# PowerCOnverter_v1_0.net
KiCad netlist of a schematic drawn in EAGLE
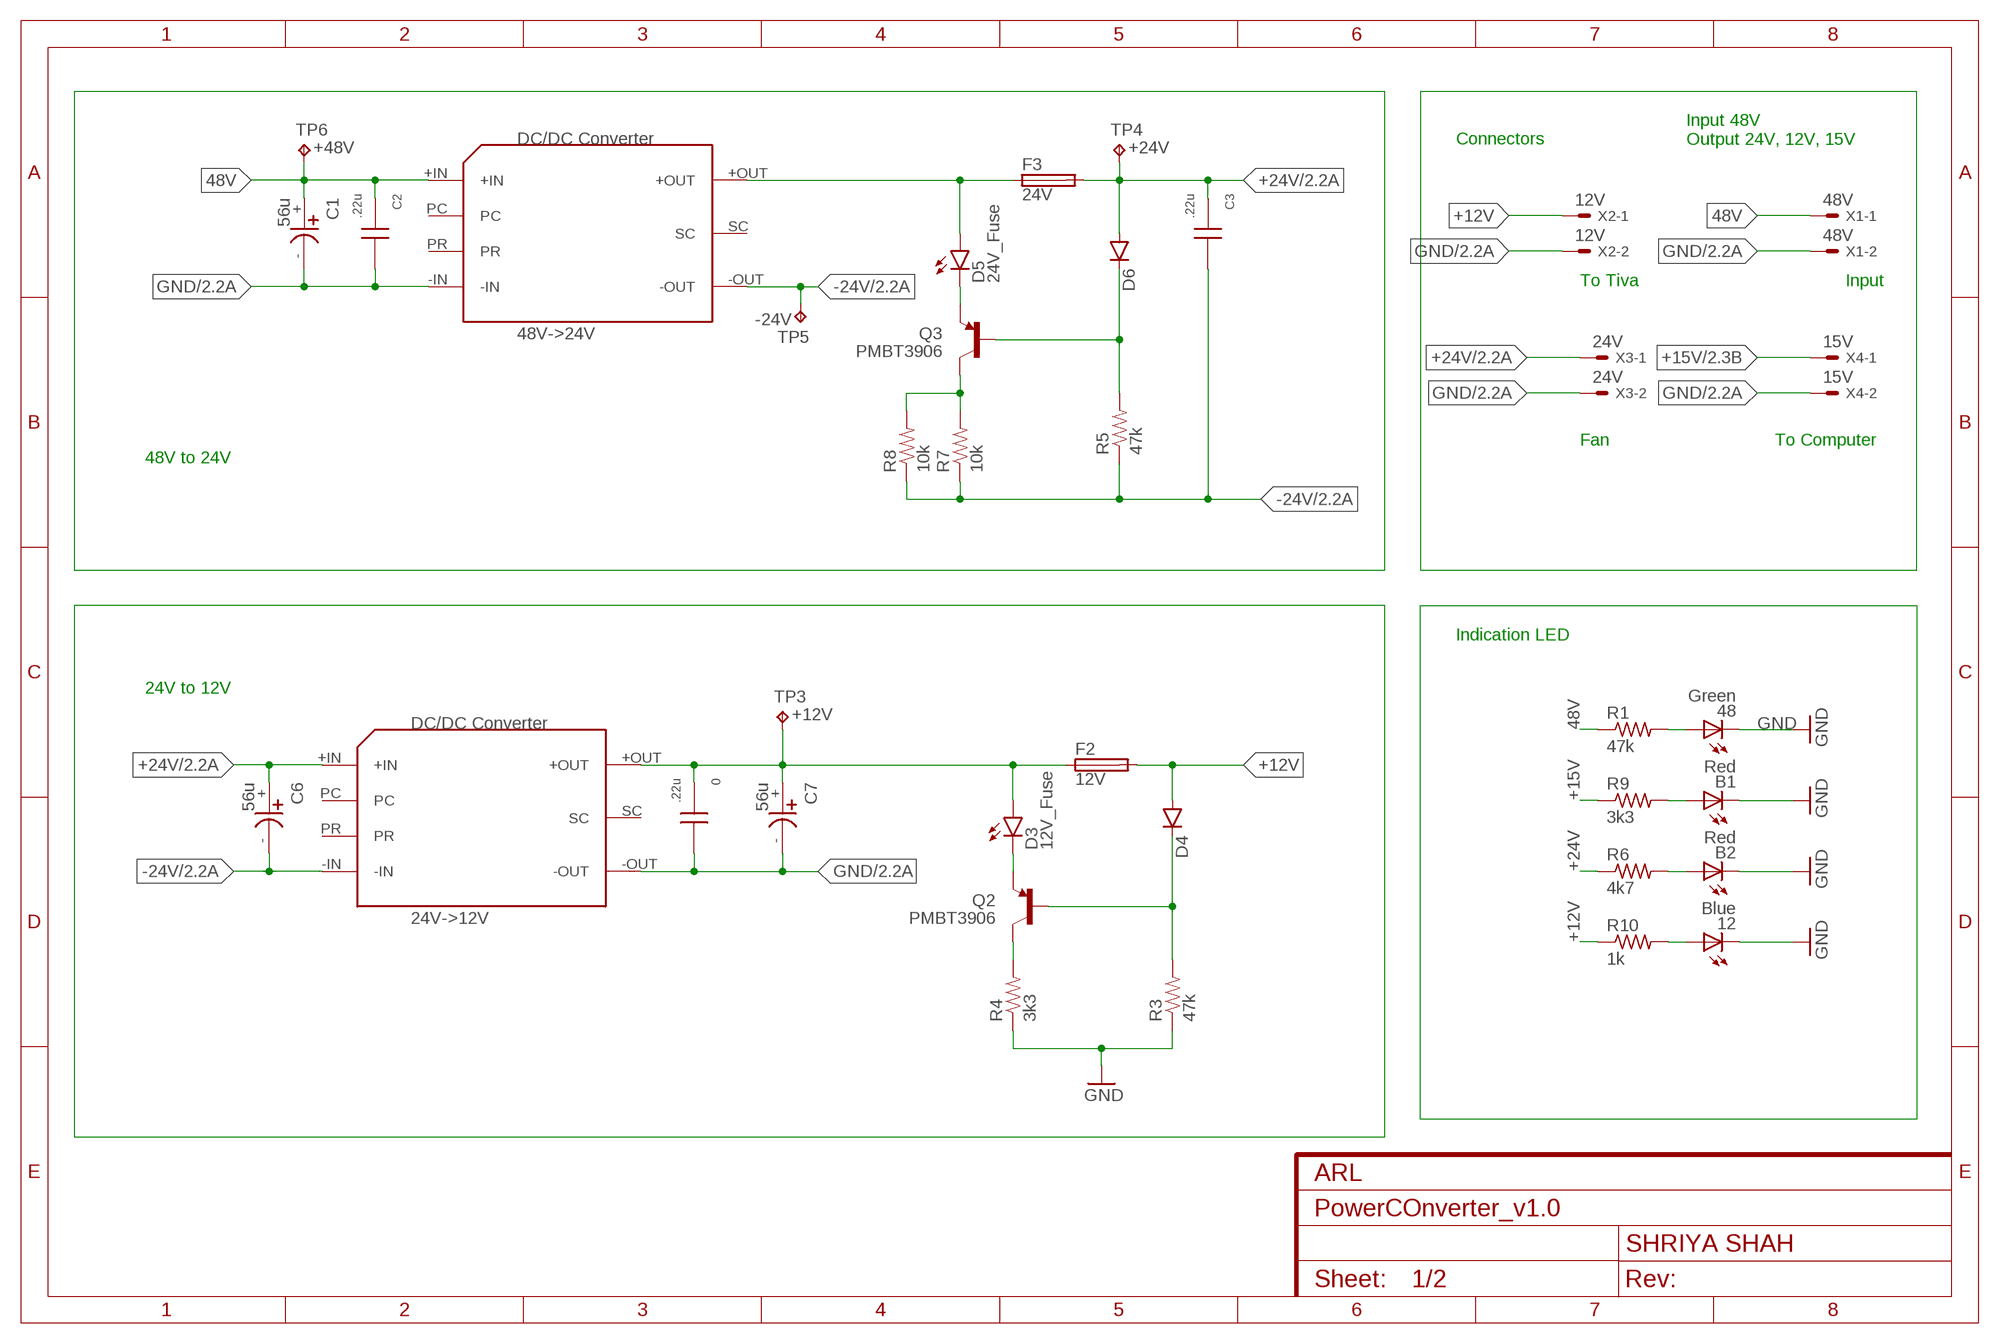
[diagram p0: schematic, sheet 1]
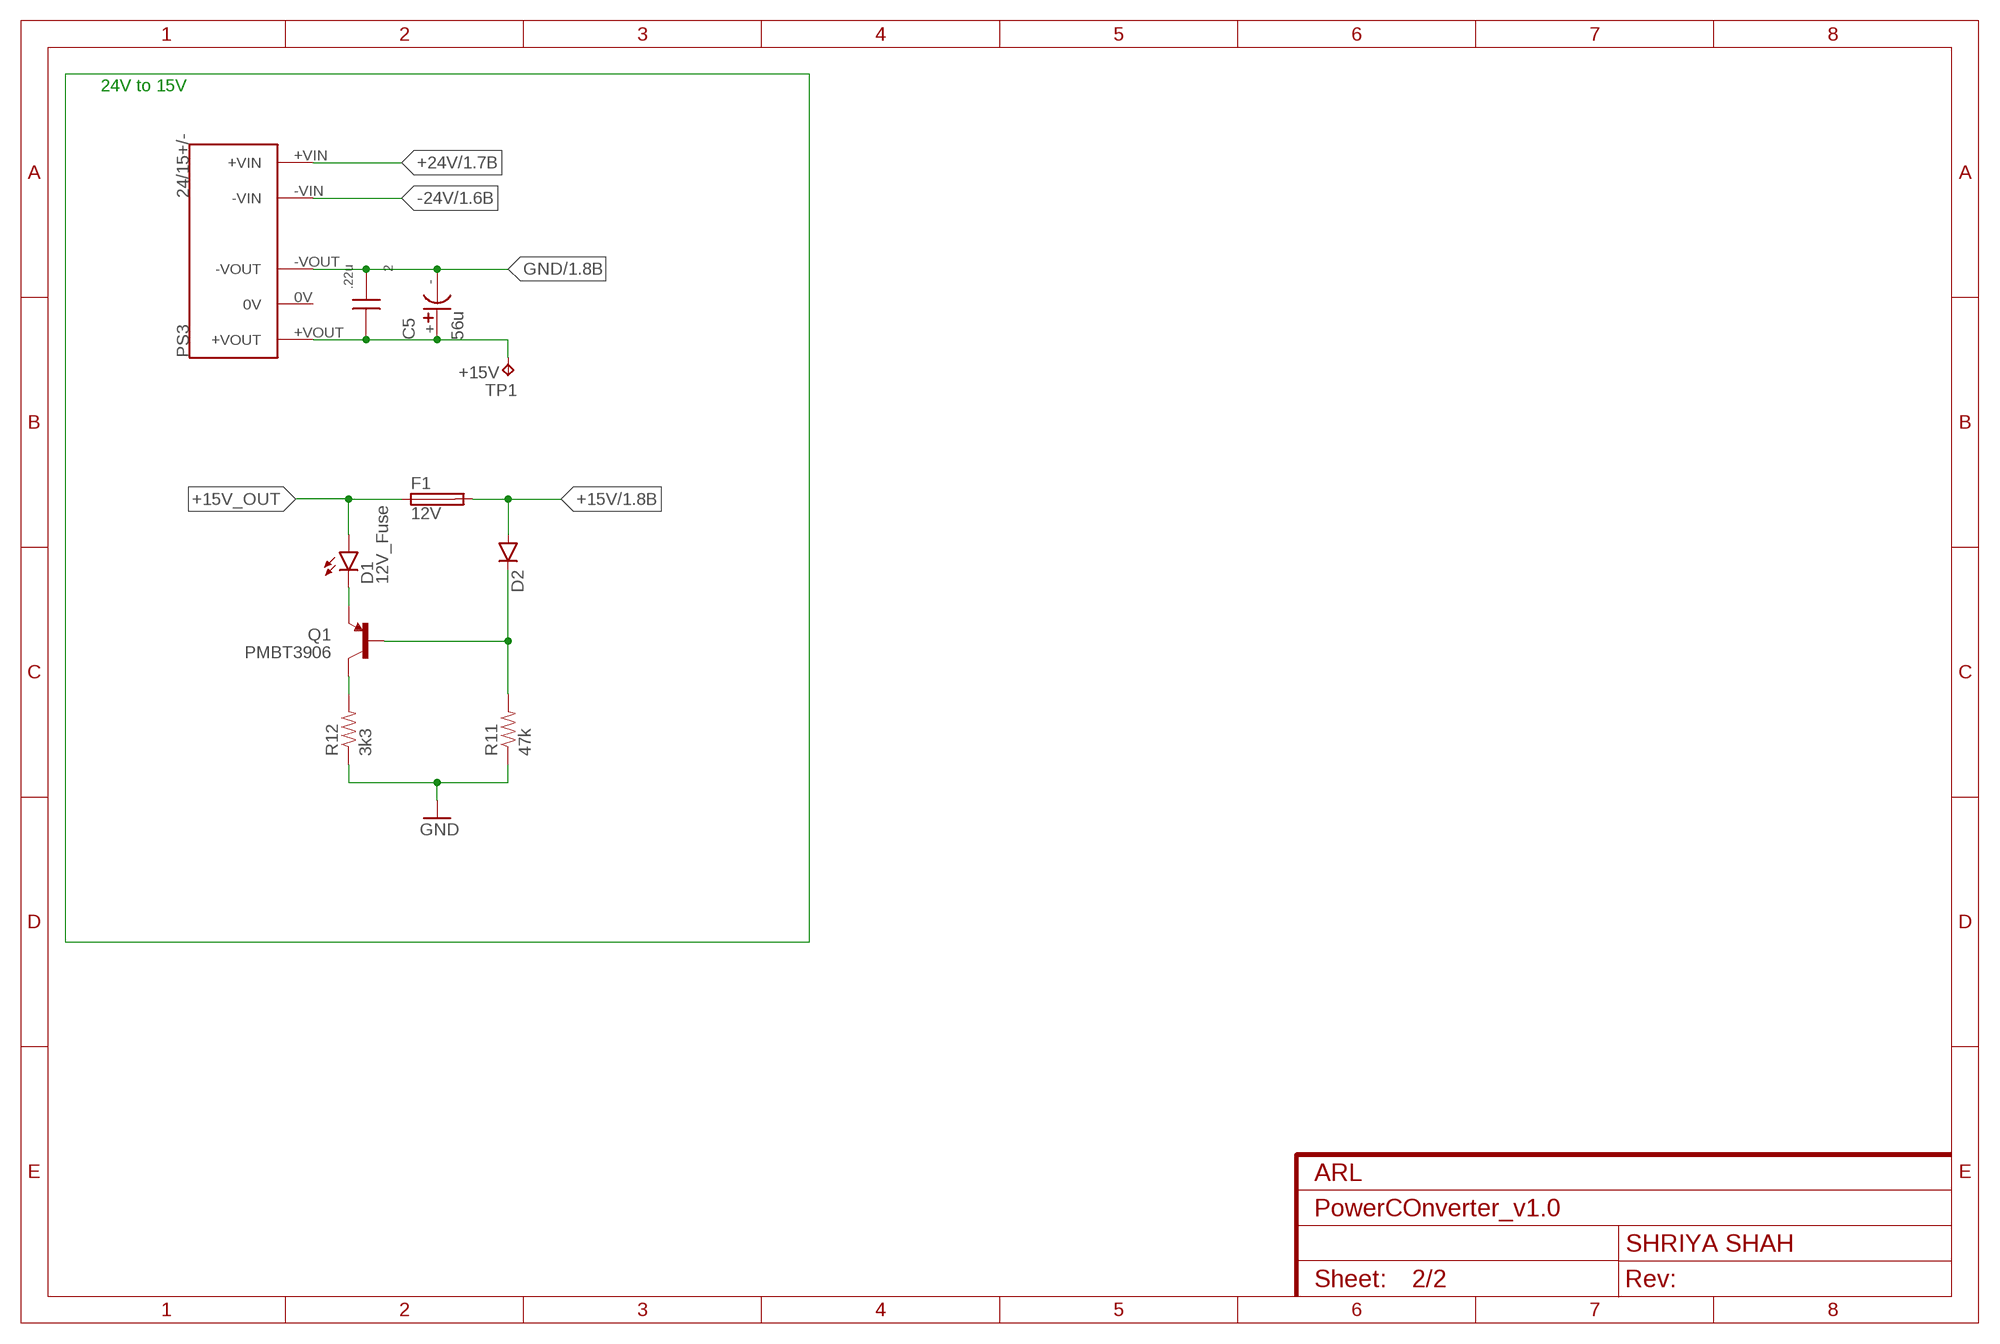
[diagram p1: schematic, sheet 2]

(export (version "E")
  (design (tool "Eeschema 10.0.6"))
  (components
    (comp (ref "2")
      (value ".22u")
      (footprint "eagle-import:CERAMIC_CAP_5MM-LEAD")
      (fields (field (name "MPN") "FK26X7R2A224K "))
      (libsource (lib "eagle-import") (part ".22U_100VDC_CERAMIC_CAP"))
    )
    (comp (ref "C5")
      (value "56u")
      (footprint "eagle-import:CAP_5MM-LEAD-10MM-D")
      (fields (field (name "MPN") "UPJ2A560MPD1TD"))
      (libsource (lib "eagle-import") (part "56U_100VDC_NICHICON"))
    )
    (comp (ref "D1")
      (value "12V_Fuse")
      (footprint "eagle-import:LED-0603")
      (fields (field (name "MPN") "LS L296-P2Q2-1-Z"))
      (libsource (lib "eagle-import") (part "RED_LED_0603"))
    )
    (comp (ref "D2")
      (value "DIODESOD")
      (footprint "eagle-import:SOD-323")
      (fields (field (name "MPN") "BAS16HT1G"))
      (libsource (lib "eagle-import") (part "DIODESOD"))
    )
    (comp (ref "F1")
      (value "12V")
      (footprint "eagle-import:LITTELFUSE_NANO")
      (fields (field (name "MPN") "01550900M"))
      (libsource (lib "eagle-import") (part "FUSELITTLEFUSE_NANO"))
    )
    (comp (ref "PS3")
      (value "24/15+/-")
      (footprint "eagle-import:MURATA_NMH")
      (fields (field (name "MPN") "NMH2415SC"))
      (libsource (lib "eagle-import") (part "MURATA_NMH2415SC"))
    )
    (comp (ref "Q1")
      (value "PMBT3906")
      (footprint "eagle-import:SOT23-3")
      (fields (field (name "MPN") " PMBT3906,215 "))
      (libsource (lib "eagle-import") (part "TRANSISTOR_PNPPMBT3906"))
    )
    (comp (ref "R11")
      (value "47k")
      (footprint "eagle-import:0603-RES")
      (fields (field (name "MPN") "CRCW060347K0JNEA"))
      (libsource (lib "eagle-import") (part "47K_RESISTOR_0603"))
    )
    (comp (ref "R12")
      (value "3k3")
      (footprint "eagle-import:0603-RES")
      (fields (field (name "MPN") "CRCW06033K30FKEA"))
      (libsource (lib "eagle-import") (part "3K3_RESISTOR_0603"))
    )
    (comp (ref "TP1")
      (value "+15V")
      (footprint "eagle-import:5000_SERIES_TESTPOINT")
      (fields (field (name "MPN") "5002"))
      (libsource (lib "eagle-import") (part "TP5000"))
    )
    (comp (ref "0")
      (value ".22u")
      (footprint "eagle-import:CERAMIC_CAP_5MM-LEAD")
      (fields (field (name "MPN") "FK26X7R2A224K "))
      (libsource (lib "eagle-import") (part ".22U_100VDC_CERAMIC_CAP"))
    )
    (comp (ref "12")
      (value "Blue")
      (footprint "eagle-import:CHIPLED_1206")
      (libsource (lib "eagle-import") (part "LEDCHIPLED_1206"))
    )
    (comp (ref "48")
      (value "Green")
      (footprint "eagle-import:CHIPLED_1206")
      (libsource (lib "eagle-import") (part "LEDCHIPLED_1206"))
    )
    (comp (ref "B1")
      (value "Red")
      (footprint "eagle-import:CHIPLED_1206")
      (libsource (lib "eagle-import") (part "LEDCHIPLED_1206"))
    )
    (comp (ref "B2")
      (value "Red")
      (footprint "eagle-import:CHIPLED_1206")
      (libsource (lib "eagle-import") (part "LEDCHIPLED_1206"))
    )
    (comp (ref "C1")
      (value "56u")
      (footprint "eagle-import:CAP_5MM-LEAD-10MM-D")
      (fields (field (name "MPN") "UPJ2A560MPD1TD"))
      (libsource (lib "eagle-import") (part "56U_100VDC_NICHICON"))
    )
    (comp (ref "C2")
      (value ".22u")
      (footprint "eagle-import:CERAMIC_CAP_5MM-LEAD")
      (fields (field (name "MPN") "FK26X7R2A224K "))
      (libsource (lib "eagle-import") (part ".22U_100VDC_CERAMIC_CAP"))
    )
    (comp (ref "C3")
      (value ".22u")
      (footprint "eagle-import:CERAMIC_CAP_5MM-LEAD")
      (fields (field (name "MPN") "FK26X7R2A224K "))
      (libsource (lib "eagle-import") (part ".22U_100VDC_CERAMIC_CAP"))
    )
    (comp (ref "C6")
      (value "56u")
      (footprint "eagle-import:CAP_5MM-LEAD-10MM-D")
      (fields (field (name "MPN") "UPJ2A560MPD1TD"))
      (libsource (lib "eagle-import") (part "56U_100VDC_NICHICON"))
    )
    (comp (ref "C7")
      (value "56u")
      (footprint "eagle-import:CAP_5MM-LEAD-10MM-D")
      (fields (field (name "MPN") "UPJ2A560MPD1TD"))
      (libsource (lib "eagle-import") (part "56U_100VDC_NICHICON"))
    )
    (comp (ref "D3")
      (value "12V_Fuse")
      (footprint "eagle-import:LED-0603")
      (fields (field (name "MPN") "LS L296-P2Q2-1-Z"))
      (libsource (lib "eagle-import") (part "RED_LED_0603"))
    )
    (comp (ref "D4")
      (value "DIODESOD")
      (footprint "eagle-import:SOD-323")
      (fields (field (name "MPN") "BAS16HT1G"))
      (libsource (lib "eagle-import") (part "DIODESOD"))
    )
    (comp (ref "D5")
      (value "24V_Fuse")
      (footprint "eagle-import:LED-0603")
      (fields (field (name "MPN") "LS L296-P2Q2-1-Z"))
      (libsource (lib "eagle-import") (part "RED_LED_0603"))
    )
    (comp (ref "D6")
      (value "DIODESOD")
      (footprint "eagle-import:SOD-323")
      (fields (field (name "MPN") "BAS16HT1G"))
      (libsource (lib "eagle-import") (part "DIODESOD"))
    )
    (comp (ref "F2")
      (value "12V")
      (footprint "eagle-import:LITTELFUSE_NANO")
      (fields (field (name "MPN") "01550900M"))
      (libsource (lib "eagle-import") (part "FUSELITTLEFUSE_NANO"))
    )
    (comp (ref "F3")
      (value "24V")
      (footprint "eagle-import:LITTELFUSE_NANO")
      (fields (field (name "MPN") "01550900M"))
      (libsource (lib "eagle-import") (part "FUSELITTLEFUSE_NANO"))
    )
    (comp (ref "PS1")
      (value "48V->24V")
      (footprint "eagle-import:VICOR_MICRO_DC_DC_CONVERTER")
      (fields (field (name "MPN") "V48C24C150BL"))
      (libsource (lib "eagle-import") (part "VICOR_MICRO_DC/DC_24V"))
    )
    (comp (ref "PS2")
      (value "24V->12V")
      (footprint "eagle-import:VICOR_MICRO_DC_DC_CONVERTER")
      (fields (field (name "MPN") "V24C12T100BL"))
      (libsource (lib "eagle-import") (part "VICOR_MICRO_DC/DC_12V"))
    )
    (comp (ref "Q2")
      (value "PMBT3906")
      (footprint "eagle-import:SOT23-3")
      (fields (field (name "MPN") " PMBT3906,215 "))
      (libsource (lib "eagle-import") (part "TRANSISTOR_PNPPMBT3906"))
    )
    (comp (ref "Q3")
      (value "PMBT3906")
      (footprint "eagle-import:SOT23-3")
      (fields (field (name "MPN") " PMBT3906,215 "))
      (libsource (lib "eagle-import") (part "TRANSISTOR_PNPPMBT3906"))
    )
    (comp (ref "R1")
      (value "47k")
      (footprint "eagle-import:M1206")
      (libsource (lib "eagle-import") (part "R-US_M1206"))
    )
    (comp (ref "R3")
      (value "47k")
      (footprint "eagle-import:0603-RES")
      (fields (field (name "MPN") "CRCW060347K0JNEA"))
      (libsource (lib "eagle-import") (part "47K_RESISTOR_0603"))
    )
    (comp (ref "R4")
      (value "3k3")
      (footprint "eagle-import:0603-RES")
      (fields (field (name "MPN") "CRCW06033K30FKEA"))
      (libsource (lib "eagle-import") (part "3K3_RESISTOR_0603"))
    )
    (comp (ref "R5")
      (value "47k")
      (footprint "eagle-import:0603-RES")
      (fields (field (name "MPN") "CRCW060347K0JNEA"))
      (libsource (lib "eagle-import") (part "47K_RESISTOR_0603"))
    )
    (comp (ref "R6")
      (value "4k7")
      (footprint "eagle-import:M1206")
      (libsource (lib "eagle-import") (part "R-US_M1206"))
    )
    (comp (ref "R7")
      (value "10k")
      (footprint "eagle-import:0603-RES")
      (fields (field (name "MPN") "CRCW060310K0FKEA"))
      (libsource (lib "eagle-import") (part "10K_RESISTOR_0603"))
    )
    (comp (ref "R8")
      (value "10k")
      (footprint "eagle-import:0603-RES")
      (fields (field (name "MPN") "CRCW060310K0FKEA"))
      (libsource (lib "eagle-import") (part "10K_RESISTOR_0603"))
    )
    (comp (ref "R9")
      (value "3k3")
      (footprint "eagle-import:M1206")
      (libsource (lib "eagle-import") (part "R-US_M1206"))
    )
    (comp (ref "R10")
      (value "1k")
      (footprint "eagle-import:M1206")
      (libsource (lib "eagle-import") (part "R-US_M1206"))
    )
    (comp (ref "TP3")
      (value "+12V")
      (footprint "eagle-import:5000_SERIES_TESTPOINT")
      (fields (field (name "MPN") "5002"))
      (libsource (lib "eagle-import") (part "TP5000"))
    )
    (comp (ref "TP4")
      (value "+24V")
      (footprint "eagle-import:5000_SERIES_TESTPOINT")
      (fields (field (name "MPN") "5002"))
      (libsource (lib "eagle-import") (part "TP5000"))
    )
    (comp (ref "TP5")
      (value "-24V")
      (footprint "eagle-import:5000_SERIES_TESTPOINT")
      (fields (field (name "MPN") "5002"))
      (libsource (lib "eagle-import") (part "TP5000"))
    )
    (comp (ref "TP6")
      (value "+48V")
      (footprint "eagle-import:5000_SERIES_TESTPOINT")
      (fields (field (name "MPN") "5002"))
      (libsource (lib "eagle-import") (part "TP5000"))
    )
    (comp (ref "X1")
      (value "48V")
      (footprint "eagle-import:5566-2")
      (fields (field (name "MF") "Molex") (field (name "MPN") "39-29-9023"))
      (libsource (lib "eagle-import") (part "5566-2"))
    )
    (comp (ref "X2")
      (value "12V")
      (footprint "eagle-import:5566-2")
      (fields (field (name "MF") "Molex") (field (name "MPN") "39-29-9023"))
      (libsource (lib "eagle-import") (part "5566-2"))
    )
    (comp (ref "X3")
      (value "24V")
      (footprint "eagle-import:5566-2")
      (fields (field (name "MF") "Molex") (field (name "MPN") "39-29-9023"))
      (libsource (lib "eagle-import") (part "5566-2"))
    )
    (comp (ref "X4")
      (value "15V")
      (footprint "eagle-import:5566-2")
      (fields (field (name "MF") "Molex") (field (name "MPN") "39-29-9023"))
      (libsource (lib "eagle-import") (part "5566-2"))
    )
  )
  (nets
    (net (code "1") (name "+12V") (class "Default")
      (node (ref "D4") (pin "A") (pinfunction "A_A") (pintype "passive"))
      (node (ref "F2") (pin "2") (pinfunction "2_2") (pintype "passive"))
      (node (ref "R10") (pin "1") (pinfunction "1_1") (pintype "passive"))
      (node (ref "X2") (pin "1") (pinfunction "S_1") (pintype "passive"))
    )
    (net (code "2") (name "+15V") (class "Default")
      (node (ref "D2") (pin "A") (pinfunction "A_A") (pintype "passive"))
      (node (ref "F1") (pin "2") (pinfunction "2_2") (pintype "passive"))
      (node (ref "R9") (pin "1") (pinfunction "1_1") (pintype "passive"))
      (node (ref "X4") (pin "1") (pinfunction "S_1") (pintype "passive"))
    )
    (net (code "3") (name "+15V_OUT") (class "Default")
      (node (ref "2") (pin "2") (pinfunction "2_2") (pintype "bidirectional"))
      (node (ref "C5") (pin "+") (pinfunction "+_+") (pintype "bidirectional"))
      (node (ref "D1") (pin "A") (pinfunction "A_A") (pintype "passive"))
      (node (ref "F1") (pin "1") (pinfunction "1_1") (pintype "passive"))
      (node (ref "PS3") (pin "+VOUT") (pinfunction "+VOUT_+VOUT") (pintype "bidirectional"))
      (node (ref "TP1") (pin "P$1") (pinfunction "TP_P$1") (pintype "input"))
    )
    (net (code "4") (name "+24V") (class "Default")
      (node (ref "C3") (pin "1") (pinfunction "1_1") (pintype "bidirectional"))
      (node (ref "C6") (pin "+") (pinfunction "+_+") (pintype "bidirectional"))
      (node (ref "D6") (pin "A") (pinfunction "A_A") (pintype "passive"))
      (node (ref "F3") (pin "2") (pinfunction "2_2") (pintype "passive"))
      (node (ref "PS2") (pin "+IN") (pinfunction "+IN_+IN") (pintype "bidirectional"))
      (node (ref "PS3") (pin "+VIN") (pinfunction "+VIN_+VIN") (pintype "bidirectional"))
      (node (ref "R6") (pin "1") (pinfunction "1_1") (pintype "passive"))
      (node (ref "TP4") (pin "P$1") (pinfunction "TP_P$1") (pintype "input"))
      (node (ref "X3") (pin "1") (pinfunction "S_1") (pintype "passive"))
    )
    (net (code "5") (name "-24V") (class "Default")
      (node (ref "C3") (pin "2") (pinfunction "2_2") (pintype "bidirectional"))
      (node (ref "C6") (pin "-") (pinfunction "-_-") (pintype "bidirectional"))
      (node (ref "PS1") (pin "-OUT") (pinfunction "-OUT_-OUT") (pintype "bidirectional"))
      (node (ref "PS2") (pin "-IN") (pinfunction "-IN_-IN") (pintype "bidirectional"))
      (node (ref "PS3") (pin "-VIN") (pinfunction "-VIN_-VIN") (pintype "bidirectional"))
      (node (ref "R5") (pin "1") (pinfunction "1_1") (pintype "passive"))
      (node (ref "R7") (pin "1") (pinfunction "1_1") (pintype "passive"))
      (node (ref "R8") (pin "1") (pinfunction "1_1") (pintype "passive"))
      (node (ref "TP5") (pin "P$1") (pinfunction "TP_P$1") (pintype "input"))
    )
    (net (code "6") (name "48V") (class "Default")
      (node (ref "C1") (pin "+") (pinfunction "+_+") (pintype "bidirectional"))
      (node (ref "C2") (pin "1") (pinfunction "1_1") (pintype "bidirectional"))
      (node (ref "PS1") (pin "+IN") (pinfunction "+IN_+IN") (pintype "bidirectional"))
      (node (ref "R1") (pin "1") (pinfunction "1_1") (pintype "passive"))
      (node (ref "TP6") (pin "P$1") (pinfunction "TP_P$1") (pintype "input"))
      (node (ref "X1") (pin "1") (pinfunction "S_1") (pintype "passive"))
    )
    (net (code "7") (name "GND") (class "Default")
      (node (ref "0") (pin "2") (pinfunction "2_2") (pintype "bidirectional"))
      (node (ref "12") (pin "C") (pinfunction "C_C") (pintype "passive"))
      (node (ref "2") (pin "1") (pinfunction "1_1") (pintype "bidirectional"))
      (node (ref "48") (pin "C") (pinfunction "C_C") (pintype "passive"))
      (node (ref "B1") (pin "C") (pinfunction "C_C") (pintype "passive"))
      (node (ref "B2") (pin "C") (pinfunction "C_C") (pintype "passive"))
      (node (ref "C1") (pin "-") (pinfunction "-_-") (pintype "bidirectional"))
      (node (ref "C2") (pin "2") (pinfunction "2_2") (pintype "bidirectional"))
      (node (ref "C5") (pin "-") (pinfunction "-_-") (pintype "bidirectional"))
      (node (ref "C7") (pin "-") (pinfunction "-_-") (pintype "bidirectional"))
      (node (ref "PS1") (pin "-IN") (pinfunction "-IN_-IN") (pintype "bidirectional"))
      (node (ref "PS2") (pin "-OUT") (pinfunction "-OUT_-OUT") (pintype "bidirectional"))
      (node (ref "PS3") (pin "-VOUT") (pinfunction "-VOUT_-VOUT") (pintype "bidirectional"))
      (node (ref "R11") (pin "1") (pinfunction "1_1") (pintype "passive"))
      (node (ref "R12") (pin "1") (pinfunction "1_1") (pintype "passive"))
      (node (ref "R3") (pin "1") (pinfunction "1_1") (pintype "passive"))
      (node (ref "R4") (pin "1") (pinfunction "1_1") (pintype "passive"))
      (node (ref "X1") (pin "2") (pinfunction "S_2") (pintype "passive"))
      (node (ref "X2") (pin "2") (pinfunction "S_2") (pintype "passive"))
      (node (ref "X3") (pin "2") (pinfunction "S_2") (pintype "passive"))
      (node (ref "X4") (pin "2") (pinfunction "S_2") (pintype "passive"))
    )
    (net (code "8") (name "Net-(12-PadA)") (class "Default")
      (node (ref "12") (pin "A") (pinfunction "A_A") (pintype "passive"))
      (node (ref "R10") (pin "2") (pinfunction "2_2") (pintype "passive"))
    )
    (net (code "9") (name "Net-(48-PadA)") (class "Default")
      (node (ref "48") (pin "A") (pinfunction "A_A") (pintype "passive"))
      (node (ref "R1") (pin "2") (pinfunction "2_2") (pintype "passive"))
    )
    (net (code "10") (name "Net-(B1-PadA)") (class "Default")
      (node (ref "B1") (pin "A") (pinfunction "A_A") (pintype "passive"))
      (node (ref "R9") (pin "2") (pinfunction "2_2") (pintype "passive"))
    )
    (net (code "11") (name "Net-(B2-PadA)") (class "Default")
      (node (ref "B2") (pin "A") (pinfunction "A_A") (pintype "passive"))
      (node (ref "R6") (pin "2") (pinfunction "2_2") (pintype "passive"))
    )
    (net (code "12") (name "Net-(D5-PadA)") (class "Default")
      (node (ref "D5") (pin "A") (pinfunction "A_A") (pintype "passive"))
      (node (ref "F3") (pin "1") (pinfunction "1_1") (pintype "passive"))
      (node (ref "PS1") (pin "+OUT") (pinfunction "+OUT_+OUT") (pintype "bidirectional"))
    )
    (net (code "13") (name "Net-(Q1-B)") (class "Default")
      (node (ref "D2") (pin "C") (pinfunction "C_C") (pintype "passive"))
      (node (ref "Q1") (pin "1") (pinfunction "B_1") (pintype "passive"))
      (node (ref "R11") (pin "2") (pinfunction "2_2") (pintype "passive"))
    )
    (net (code "14") (name "Net-(Q1-C)") (class "Default")
      (node (ref "Q1") (pin "3") (pinfunction "C_3") (pintype "passive"))
      (node (ref "R12") (pin "2") (pinfunction "2_2") (pintype "passive"))
    )
    (net (code "15") (name "Net-(Q1-E)") (class "Default")
      (node (ref "D1") (pin "C") (pinfunction "C_C") (pintype "passive"))
      (node (ref "Q1") (pin "2") (pinfunction "E_2") (pintype "passive"))
    )
    (net (code "16") (name "Net-(Q2-B)") (class "Default")
      (node (ref "D4") (pin "C") (pinfunction "C_C") (pintype "passive"))
      (node (ref "Q2") (pin "1") (pinfunction "B_1") (pintype "passive"))
      (node (ref "R3") (pin "2") (pinfunction "2_2") (pintype "passive"))
    )
    (net (code "17") (name "Net-(Q2-C)") (class "Default")
      (node (ref "Q2") (pin "3") (pinfunction "C_3") (pintype "passive"))
      (node (ref "R4") (pin "2") (pinfunction "2_2") (pintype "passive"))
    )
    (net (code "18") (name "Net-(Q2-E)") (class "Default")
      (node (ref "D3") (pin "C") (pinfunction "C_C") (pintype "passive"))
      (node (ref "Q2") (pin "2") (pinfunction "E_2") (pintype "passive"))
    )
    (net (code "19") (name "Net-(Q3-B)") (class "Default")
      (node (ref "D6") (pin "C") (pinfunction "C_C") (pintype "passive"))
      (node (ref "Q3") (pin "1") (pinfunction "B_1") (pintype "passive"))
      (node (ref "R5") (pin "2") (pinfunction "2_2") (pintype "passive"))
    )
    (net (code "20") (name "Net-(Q3-C)") (class "Default")
      (node (ref "Q3") (pin "3") (pinfunction "C_3") (pintype "passive"))
      (node (ref "R7") (pin "2") (pinfunction "2_2") (pintype "passive"))
      (node (ref "R8") (pin "2") (pinfunction "2_2") (pintype "passive"))
    )
    (net (code "21") (name "Net-(Q3-E)") (class "Default")
      (node (ref "D5") (pin "C") (pinfunction "C_C") (pintype "passive"))
      (node (ref "Q3") (pin "2") (pinfunction "E_2") (pintype "passive"))
    )
    (net (code "22") (name "Net-(TP3-TP)") (class "Default")
      (node (ref "0") (pin "1") (pinfunction "1_1") (pintype "bidirectional"))
      (node (ref "C7") (pin "+") (pinfunction "+_+") (pintype "bidirectional"))
      (node (ref "D3") (pin "A") (pinfunction "A_A") (pintype "passive"))
      (node (ref "F2") (pin "1") (pinfunction "1_1") (pintype "passive"))
      (node (ref "PS2") (pin "+OUT") (pinfunction "+OUT_+OUT") (pintype "bidirectional"))
      (node (ref "TP3") (pin "P$1") (pinfunction "TP_P$1") (pintype "input"))
    )
    (net (code "23") (name "unconnected-(PS1-PadPC)") (class "Default")
      (node (ref "PS1") (pin "PC") (pinfunction "PC_PC") (pintype "bidirectional"))
    )
    (net (code "24") (name "unconnected-(PS1-PadPR)") (class "Default")
      (node (ref "PS1") (pin "PR") (pinfunction "PR_PR") (pintype "bidirectional"))
    )
    (net (code "25") (name "unconnected-(PS1-PadSC)") (class "Default")
      (node (ref "PS1") (pin "SC") (pinfunction "SC_SC") (pintype "bidirectional"))
    )
    (net (code "26") (name "unconnected-(PS2-PadPC)") (class "Default")
      (node (ref "PS2") (pin "PC") (pinfunction "PC_PC") (pintype "bidirectional"))
    )
    (net (code "27") (name "unconnected-(PS2-PadPR)") (class "Default")
      (node (ref "PS2") (pin "PR") (pinfunction "PR_PR") (pintype "bidirectional"))
    )
    (net (code "28") (name "unconnected-(PS2-PadSC)") (class "Default")
      (node (ref "PS2") (pin "SC") (pinfunction "SC_SC") (pintype "bidirectional"))
    )
    (net (code "29") (name "unconnected-(PS3-Pad0V)") (class "Default")
      (node (ref "PS3") (pin "0V") (pinfunction "0V_0V") (pintype "bidirectional"))
    )
  )
)
